# 3rd_layer.net
KiCad netlist of a schematic drawn in EAGLE
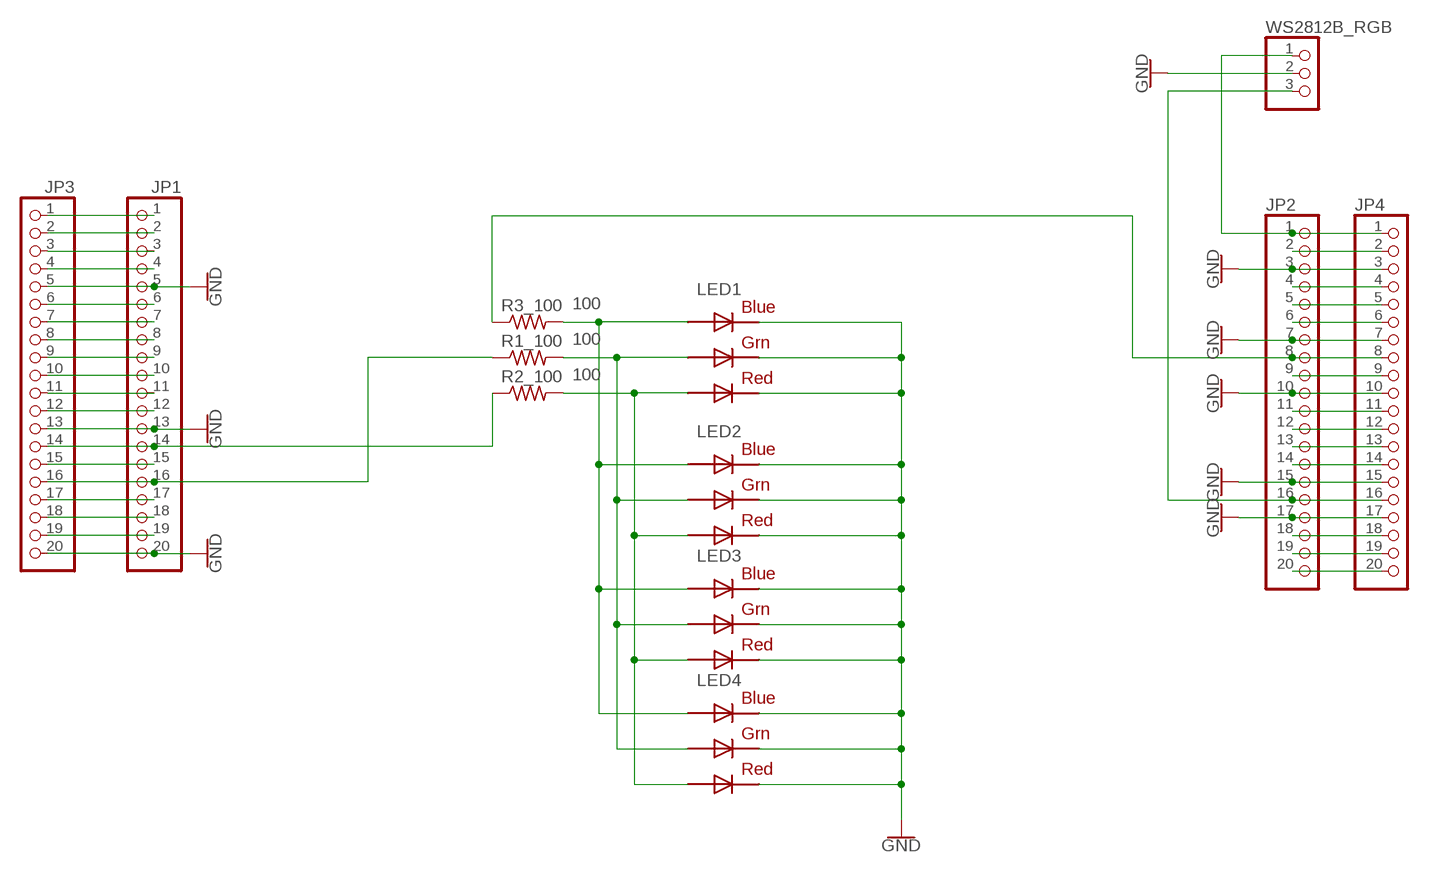
[diagram p0: schematic, sheet 1]

(export (version "E")
  (design (tool "Eeschema 10.0.6"))
  (components
    (comp (ref "JP1")
      (value "PINHD-1X20")
      (footprint "eagle-import:1X20")
      (libsource (lib "eagle-import") (part "PINHD-1X20"))
    )
    (comp (ref "JP2")
      (value "PINHD-1X20")
      (footprint "eagle-import:1X20")
      (libsource (lib "eagle-import") (part "PINHD-1X20"))
    )
    (comp (ref "JP3")
      (value "PINHD-1X20")
      (footprint "eagle-import:1X20")
      (libsource (lib "eagle-import") (part "PINHD-1X20"))
    )
    (comp (ref "JP4")
      (value "PINHD-1X20")
      (footprint "eagle-import:1X20")
      (libsource (lib "eagle-import") (part "PINHD-1X20"))
    )
    (comp (ref "LED1")
      (value "RGBLED5050")
      (footprint "eagle-import:RGBLED5050")
      (libsource (lib "eagle-import") (part "RGBLED5050"))
    )
    (comp (ref "LED2")
      (value "RGBLED5050")
      (footprint "eagle-import:RGBLED5050")
      (libsource (lib "eagle-import") (part "RGBLED5050"))
    )
    (comp (ref "LED3")
      (value "RGBLED5050")
      (footprint "eagle-import:RGBLED5050")
      (libsource (lib "eagle-import") (part "RGBLED5050"))
    )
    (comp (ref "LED4")
      (value "RGBLED5050")
      (footprint "eagle-import:RGBLED5050")
      (libsource (lib "eagle-import") (part "RGBLED5050"))
    )
    (comp (ref "R1_100")
      (value "100")
      (footprint "eagle-import:R0603")
      (libsource (lib "eagle-import") (part "R-US_R0603"))
    )
    (comp (ref "R2_100")
      (value "100")
      (footprint "eagle-import:R0603")
      (libsource (lib "eagle-import") (part "R-US_R0603"))
    )
    (comp (ref "R3_100")
      (value "100")
      (footprint "eagle-import:R0603")
      (libsource (lib "eagle-import") (part "R-US_R0603"))
    )
    (comp (ref "WS2812B_RGB")
      (value "PINHD-1X3/90")
      (footprint "eagle-import:1X03_90")
      (libsource (lib "eagle-import") (part "PINHD-1X3/90"))
    )
  )
  (nets
    (net (code "1") (name "GND") (class "Default")
      (node (ref "JP1") (pin "13") (pinfunction "13_13") (pintype "passive"))
      (node (ref "JP1") (pin "20") (pinfunction "20_20") (pintype "passive"))
      (node (ref "JP1") (pin "5") (pinfunction "5_5") (pintype "passive"))
      (node (ref "JP2") (pin "10") (pinfunction "10_10") (pintype "passive"))
      (node (ref "JP2") (pin "15") (pinfunction "15_15") (pintype "passive"))
      (node (ref "JP2") (pin "17") (pinfunction "17_17") (pintype "passive"))
      (node (ref "JP2") (pin "3") (pinfunction "3_3") (pintype "passive"))
      (node (ref "JP2") (pin "7") (pinfunction "7_7") (pintype "passive"))
      (node (ref "JP3") (pin "13") (pinfunction "13_13") (pintype "passive"))
      (node (ref "JP3") (pin "20") (pinfunction "20_20") (pintype "passive"))
      (node (ref "JP3") (pin "5") (pinfunction "5_5") (pintype "passive"))
      (node (ref "JP4") (pin "10") (pinfunction "10_10") (pintype "passive"))
      (node (ref "JP4") (pin "15") (pinfunction "15_15") (pintype "passive"))
      (node (ref "JP4") (pin "17") (pinfunction "17_17") (pintype "passive"))
      (node (ref "JP4") (pin "3") (pinfunction "3_3") (pintype "passive"))
      (node (ref "JP4") (pin "7") (pinfunction "7_7") (pintype "passive"))
      (node (ref "LED1") (pin "4") (pinfunction "BLUE_C_4") (pintype "bidirectional"))
      (node (ref "LED1") (pin "5") (pinfunction "RED_C_5") (pintype "bidirectional"))
      (node (ref "LED1") (pin "6") (pinfunction "GREEN_C_6") (pintype "bidirectional"))
      (node (ref "LED2") (pin "4") (pinfunction "BLUE_C_4") (pintype "bidirectional"))
      (node (ref "LED2") (pin "5") (pinfunction "RED_C_5") (pintype "bidirectional"))
      (node (ref "LED2") (pin "6") (pinfunction "GREEN_C_6") (pintype "bidirectional"))
      (node (ref "LED3") (pin "4") (pinfunction "BLUE_C_4") (pintype "bidirectional"))
      (node (ref "LED3") (pin "5") (pinfunction "RED_C_5") (pintype "bidirectional"))
      (node (ref "LED3") (pin "6") (pinfunction "GREEN_C_6") (pintype "bidirectional"))
      (node (ref "LED4") (pin "4") (pinfunction "BLUE_C_4") (pintype "bidirectional"))
      (node (ref "LED4") (pin "5") (pinfunction "RED_C_5") (pintype "bidirectional"))
      (node (ref "LED4") (pin "6") (pinfunction "GREEN_C_6") (pintype "bidirectional"))
      (node (ref "WS2812B_RGB") (pin "2") (pinfunction "2_2") (pintype "passive"))
    )
    (net (code "2") (name "Net-(JP1-Pad1)") (class "Default")
      (node (ref "JP1") (pin "1") (pinfunction "1_1") (pintype "passive"))
      (node (ref "JP3") (pin "1") (pinfunction "1_1") (pintype "passive"))
    )
    (net (code "3") (name "Net-(JP1-Pad2)") (class "Default")
      (node (ref "JP1") (pin "2") (pinfunction "2_2") (pintype "passive"))
      (node (ref "JP3") (pin "2") (pinfunction "2_2") (pintype "passive"))
    )
    (net (code "4") (name "Net-(JP1-Pad3)") (class "Default")
      (node (ref "JP1") (pin "3") (pinfunction "3_3") (pintype "passive"))
      (node (ref "JP3") (pin "3") (pinfunction "3_3") (pintype "passive"))
    )
    (net (code "5") (name "Net-(JP1-Pad4)") (class "Default")
      (node (ref "JP1") (pin "4") (pinfunction "4_4") (pintype "passive"))
      (node (ref "JP3") (pin "4") (pinfunction "4_4") (pintype "passive"))
    )
    (net (code "6") (name "Net-(JP1-Pad6)") (class "Default")
      (node (ref "JP1") (pin "6") (pinfunction "6_6") (pintype "passive"))
      (node (ref "JP3") (pin "6") (pinfunction "6_6") (pintype "passive"))
    )
    (net (code "7") (name "Net-(JP1-Pad7)") (class "Default")
      (node (ref "JP1") (pin "7") (pinfunction "7_7") (pintype "passive"))
      (node (ref "JP3") (pin "7") (pinfunction "7_7") (pintype "passive"))
    )
    (net (code "8") (name "Net-(JP1-Pad8)") (class "Default")
      (node (ref "JP1") (pin "8") (pinfunction "8_8") (pintype "passive"))
      (node (ref "JP3") (pin "8") (pinfunction "8_8") (pintype "passive"))
    )
    (net (code "9") (name "Net-(JP1-Pad9)") (class "Default")
      (node (ref "JP1") (pin "9") (pinfunction "9_9") (pintype "passive"))
      (node (ref "JP3") (pin "9") (pinfunction "9_9") (pintype "passive"))
    )
    (net (code "10") (name "Net-(JP1-Pad10)") (class "Default")
      (node (ref "JP1") (pin "10") (pinfunction "10_10") (pintype "passive"))
      (node (ref "JP3") (pin "10") (pinfunction "10_10") (pintype "passive"))
    )
    (net (code "11") (name "Net-(JP1-Pad11)") (class "Default")
      (node (ref "JP1") (pin "11") (pinfunction "11_11") (pintype "passive"))
      (node (ref "JP3") (pin "11") (pinfunction "11_11") (pintype "passive"))
    )
    (net (code "12") (name "Net-(JP1-Pad12)") (class "Default")
      (node (ref "JP1") (pin "12") (pinfunction "12_12") (pintype "passive"))
      (node (ref "JP3") (pin "12") (pinfunction "12_12") (pintype "passive"))
    )
    (net (code "13") (name "Net-(JP1-Pad14)") (class "Default")
      (node (ref "JP1") (pin "14") (pinfunction "14_14") (pintype "passive"))
      (node (ref "JP3") (pin "14") (pinfunction "14_14") (pintype "passive"))
      (node (ref "R2_100") (pin "1") (pinfunction "1_1") (pintype "passive"))
    )
    (net (code "14") (name "Net-(JP1-Pad15)") (class "Default")
      (node (ref "JP1") (pin "15") (pinfunction "15_15") (pintype "passive"))
      (node (ref "JP3") (pin "15") (pinfunction "15_15") (pintype "passive"))
    )
    (net (code "15") (name "Net-(JP1-Pad16)") (class "Default")
      (node (ref "JP1") (pin "16") (pinfunction "16_16") (pintype "passive"))
      (node (ref "JP3") (pin "16") (pinfunction "16_16") (pintype "passive"))
      (node (ref "R1_100") (pin "1") (pinfunction "1_1") (pintype "passive"))
    )
    (net (code "16") (name "Net-(JP1-Pad17)") (class "Default")
      (node (ref "JP1") (pin "17") (pinfunction "17_17") (pintype "passive"))
      (node (ref "JP3") (pin "17") (pinfunction "17_17") (pintype "passive"))
    )
    (net (code "17") (name "Net-(JP1-Pad18)") (class "Default")
      (node (ref "JP1") (pin "18") (pinfunction "18_18") (pintype "passive"))
      (node (ref "JP3") (pin "18") (pinfunction "18_18") (pintype "passive"))
    )
    (net (code "18") (name "Net-(JP1-Pad19)") (class "Default")
      (node (ref "JP1") (pin "19") (pinfunction "19_19") (pintype "passive"))
      (node (ref "JP3") (pin "19") (pinfunction "19_19") (pintype "passive"))
    )
    (net (code "19") (name "Net-(JP2-Pad1)") (class "Default")
      (node (ref "JP2") (pin "1") (pinfunction "1_1") (pintype "passive"))
      (node (ref "JP4") (pin "1") (pinfunction "1_1") (pintype "passive"))
      (node (ref "WS2812B_RGB") (pin "1") (pinfunction "1_1") (pintype "passive"))
    )
    (net (code "20") (name "Net-(JP2-Pad2)") (class "Default")
      (node (ref "JP2") (pin "2") (pinfunction "2_2") (pintype "passive"))
      (node (ref "JP4") (pin "2") (pinfunction "2_2") (pintype "passive"))
    )
    (net (code "21") (name "Net-(JP2-Pad4)") (class "Default")
      (node (ref "JP2") (pin "4") (pinfunction "4_4") (pintype "passive"))
      (node (ref "JP4") (pin "4") (pinfunction "4_4") (pintype "passive"))
    )
    (net (code "22") (name "Net-(JP2-Pad5)") (class "Default")
      (node (ref "JP2") (pin "5") (pinfunction "5_5") (pintype "passive"))
      (node (ref "JP4") (pin "5") (pinfunction "5_5") (pintype "passive"))
    )
    (net (code "23") (name "Net-(JP2-Pad6)") (class "Default")
      (node (ref "JP2") (pin "6") (pinfunction "6_6") (pintype "passive"))
      (node (ref "JP4") (pin "6") (pinfunction "6_6") (pintype "passive"))
    )
    (net (code "24") (name "Net-(JP2-Pad8)") (class "Default")
      (node (ref "JP2") (pin "8") (pinfunction "8_8") (pintype "passive"))
      (node (ref "JP4") (pin "8") (pinfunction "8_8") (pintype "passive"))
      (node (ref "R3_100") (pin "1") (pinfunction "1_1") (pintype "passive"))
    )
    (net (code "25") (name "Net-(JP2-Pad9)") (class "Default")
      (node (ref "JP2") (pin "9") (pinfunction "9_9") (pintype "passive"))
      (node (ref "JP4") (pin "9") (pinfunction "9_9") (pintype "passive"))
    )
    (net (code "26") (name "Net-(JP2-Pad11)") (class "Default")
      (node (ref "JP2") (pin "11") (pinfunction "11_11") (pintype "passive"))
      (node (ref "JP4") (pin "11") (pinfunction "11_11") (pintype "passive"))
    )
    (net (code "27") (name "Net-(JP2-Pad12)") (class "Default")
      (node (ref "JP2") (pin "12") (pinfunction "12_12") (pintype "passive"))
      (node (ref "JP4") (pin "12") (pinfunction "12_12") (pintype "passive"))
    )
    (net (code "28") (name "Net-(JP2-Pad13)") (class "Default")
      (node (ref "JP2") (pin "13") (pinfunction "13_13") (pintype "passive"))
      (node (ref "JP4") (pin "13") (pinfunction "13_13") (pintype "passive"))
    )
    (net (code "29") (name "Net-(JP2-Pad14)") (class "Default")
      (node (ref "JP2") (pin "14") (pinfunction "14_14") (pintype "passive"))
      (node (ref "JP4") (pin "14") (pinfunction "14_14") (pintype "passive"))
    )
    (net (code "30") (name "Net-(JP2-Pad16)") (class "Default")
      (node (ref "JP2") (pin "16") (pinfunction "16_16") (pintype "passive"))
      (node (ref "JP4") (pin "16") (pinfunction "16_16") (pintype "passive"))
      (node (ref "WS2812B_RGB") (pin "3") (pinfunction "3_3") (pintype "passive"))
    )
    (net (code "31") (name "Net-(JP2-Pad18)") (class "Default")
      (node (ref "JP2") (pin "18") (pinfunction "18_18") (pintype "passive"))
      (node (ref "JP4") (pin "18") (pinfunction "18_18") (pintype "passive"))
    )
    (net (code "32") (name "Net-(JP2-Pad19)") (class "Default")
      (node (ref "JP2") (pin "19") (pinfunction "19_19") (pintype "passive"))
      (node (ref "JP4") (pin "19") (pinfunction "19_19") (pintype "passive"))
    )
    (net (code "33") (name "Net-(JP2-Pad20)") (class "Default")
      (node (ref "JP2") (pin "20") (pinfunction "20_20") (pintype "passive"))
      (node (ref "JP4") (pin "20") (pinfunction "20_20") (pintype "passive"))
    )
    (net (code "34") (name "Net-(LED1-BLUE_A)") (class "Default")
      (node (ref "LED1") (pin "3") (pinfunction "BLUE_A_3") (pintype "bidirectional"))
      (node (ref "LED2") (pin "3") (pinfunction "BLUE_A_3") (pintype "bidirectional"))
      (node (ref "LED3") (pin "3") (pinfunction "BLUE_A_3") (pintype "bidirectional"))
      (node (ref "LED4") (pin "3") (pinfunction "BLUE_A_3") (pintype "bidirectional"))
      (node (ref "R3_100") (pin "2") (pinfunction "2_2") (pintype "passive"))
    )
    (net (code "35") (name "Net-(LED1-GREEN_A)") (class "Default")
      (node (ref "LED1") (pin "1") (pinfunction "GREEN_A_1") (pintype "bidirectional"))
      (node (ref "LED2") (pin "1") (pinfunction "GREEN_A_1") (pintype "bidirectional"))
      (node (ref "LED3") (pin "1") (pinfunction "GREEN_A_1") (pintype "bidirectional"))
      (node (ref "LED4") (pin "1") (pinfunction "GREEN_A_1") (pintype "bidirectional"))
      (node (ref "R1_100") (pin "2") (pinfunction "2_2") (pintype "passive"))
    )
    (net (code "36") (name "Net-(LED1-RED_A)") (class "Default")
      (node (ref "LED1") (pin "2") (pinfunction "RED_A_2") (pintype "bidirectional"))
      (node (ref "LED2") (pin "2") (pinfunction "RED_A_2") (pintype "bidirectional"))
      (node (ref "LED3") (pin "2") (pinfunction "RED_A_2") (pintype "bidirectional"))
      (node (ref "LED4") (pin "2") (pinfunction "RED_A_2") (pintype "bidirectional"))
      (node (ref "R2_100") (pin "2") (pinfunction "2_2") (pintype "passive"))
    )
  )
)
